# AINx4.net
KiCad netlist of a schematic drawn in EAGLE
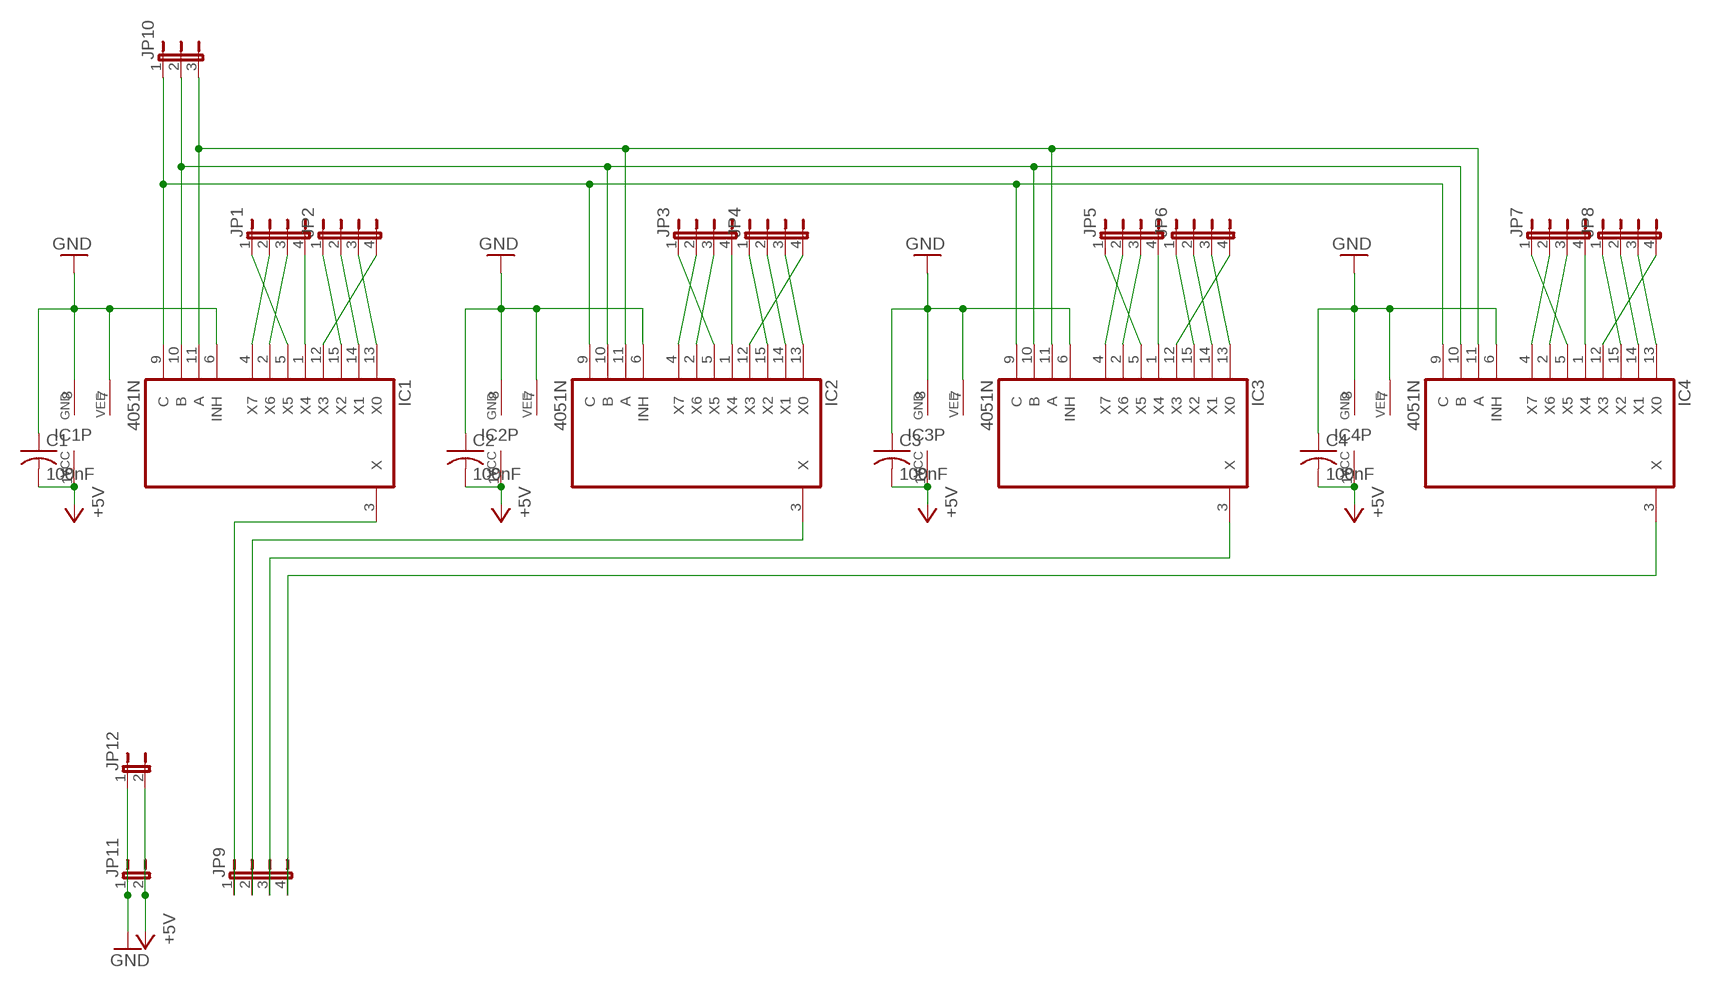
[diagram p0: schematic, sheet 1]

(export (version "E")
  (design (tool "Eeschema 10.0.6"))
  (components
    (comp (ref "C1")
      (value "100nF")
      (footprint "eagle-import:C025-025X050")
      (libsource (lib "eagle-import") (part "C-US025-025X050"))
    )
    (comp (ref "C2")
      (value "100nF")
      (footprint "eagle-import:C025-025X050")
      (libsource (lib "eagle-import") (part "C-US025-025X050"))
    )
    (comp (ref "C3")
      (value "100nF")
      (footprint "eagle-import:C025-025X050")
      (libsource (lib "eagle-import") (part "C-US025-025X050"))
    )
    (comp (ref "C4")
      (value "100nF")
      (footprint "eagle-import:C025-025X050")
      (libsource (lib "eagle-import") (part "C-US025-025X050"))
    )
    (comp (ref "IC1")
      (value "4051N")
      (footprint "eagle-import:DIL16")
      (libsource (lib "eagle-import") (part "4051N"))
    )
    (comp (ref "IC2")
      (value "4051N")
      (footprint "eagle-import:DIL16")
      (libsource (lib "eagle-import") (part "4051N"))
    )
    (comp (ref "IC3")
      (value "4051N")
      (footprint "eagle-import:DIL16")
      (libsource (lib "eagle-import") (part "4051N"))
    )
    (comp (ref "IC4")
      (value "4051N")
      (footprint "eagle-import:DIL16")
      (libsource (lib "eagle-import") (part "4051N"))
    )
    (comp (ref "JP1")
      (value "JP4E")
      (footprint "eagle-import:JP4")
      (libsource (lib "eagle-import") (part "JP4E"))
    )
    (comp (ref "JP2")
      (value "JP4E")
      (footprint "eagle-import:JP4")
      (libsource (lib "eagle-import") (part "JP4E"))
    )
    (comp (ref "JP3")
      (value "JP4E")
      (footprint "eagle-import:JP4")
      (libsource (lib "eagle-import") (part "JP4E"))
    )
    (comp (ref "JP4")
      (value "JP4E")
      (footprint "eagle-import:JP4")
      (libsource (lib "eagle-import") (part "JP4E"))
    )
    (comp (ref "JP5")
      (value "JP4E")
      (footprint "eagle-import:JP4")
      (libsource (lib "eagle-import") (part "JP4E"))
    )
    (comp (ref "JP6")
      (value "JP4E")
      (footprint "eagle-import:JP4")
      (libsource (lib "eagle-import") (part "JP4E"))
    )
    (comp (ref "JP7")
      (value "JP4E")
      (footprint "eagle-import:JP4")
      (libsource (lib "eagle-import") (part "JP4E"))
    )
    (comp (ref "JP8")
      (value "JP4E")
      (footprint "eagle-import:JP4")
      (libsource (lib "eagle-import") (part "JP4E"))
    )
    (comp (ref "JP9")
      (value "JP4E")
      (footprint "eagle-import:JP4")
      (libsource (lib "eagle-import") (part "JP4E"))
    )
    (comp (ref "JP10")
      (value "JP2E")
      (footprint "eagle-import:JP2")
      (libsource (lib "eagle-import") (part "JP2E"))
    )
    (comp (ref "JP11")
      (value "JP1E")
      (footprint "eagle-import:JP1")
      (libsource (lib "eagle-import") (part "JP1E"))
    )
    (comp (ref "JP12")
      (value "JP1E")
      (footprint "eagle-import:JP1")
      (libsource (lib "eagle-import") (part "JP1E"))
    )
  )
  (nets
    (net (code "1") (name "+5V") (class "Default")
      (node (ref "C1") (pin "2") (pinfunction "2_2") (pintype "passive"))
      (node (ref "C2") (pin "2") (pinfunction "2_2") (pintype "passive"))
      (node (ref "C3") (pin "2") (pinfunction "2_2") (pintype "passive"))
      (node (ref "C4") (pin "2") (pinfunction "2_2") (pintype "passive"))
      (node (ref "IC1") (pin "16") (pinfunction "VCC_16") (pintype "power_in"))
      (node (ref "IC2") (pin "16") (pinfunction "VCC_16") (pintype "power_in"))
      (node (ref "IC3") (pin "16") (pinfunction "VCC_16") (pintype "power_in"))
      (node (ref "IC4") (pin "16") (pinfunction "VCC_16") (pintype "power_in"))
      (node (ref "JP11") (pin "2") (pinfunction "2_2") (pintype "passive"))
      (node (ref "JP12") (pin "2") (pinfunction "2_2") (pintype "passive"))
    )
    (net (code "2") (name "GND") (class "Default")
      (node (ref "C1") (pin "1") (pinfunction "1_1") (pintype "passive"))
      (node (ref "C2") (pin "1") (pinfunction "1_1") (pintype "passive"))
      (node (ref "C3") (pin "1") (pinfunction "1_1") (pintype "passive"))
      (node (ref "C4") (pin "1") (pinfunction "1_1") (pintype "passive"))
      (node (ref "IC1") (pin "6") (pinfunction "INH_6") (pintype "input"))
      (node (ref "IC1") (pin "7") (pinfunction "VEE_7") (pintype "power_in"))
      (node (ref "IC1") (pin "8") (pinfunction "GND_8") (pintype "power_in"))
      (node (ref "IC2") (pin "6") (pinfunction "INH_6") (pintype "input"))
      (node (ref "IC2") (pin "7") (pinfunction "VEE_7") (pintype "power_in"))
      (node (ref "IC2") (pin "8") (pinfunction "GND_8") (pintype "power_in"))
      (node (ref "IC3") (pin "6") (pinfunction "INH_6") (pintype "input"))
      (node (ref "IC3") (pin "7") (pinfunction "VEE_7") (pintype "power_in"))
      (node (ref "IC3") (pin "8") (pinfunction "GND_8") (pintype "power_in"))
      (node (ref "IC4") (pin "6") (pinfunction "INH_6") (pintype "input"))
      (node (ref "IC4") (pin "7") (pinfunction "VEE_7") (pintype "power_in"))
      (node (ref "IC4") (pin "8") (pinfunction "GND_8") (pintype "power_in"))
      (node (ref "JP11") (pin "1") (pinfunction "1_1") (pintype "passive"))
      (node (ref "JP12") (pin "1") (pinfunction "1_1") (pintype "passive"))
    )
    (net (code "3") (name "Net-(IC1A-A)") (class "Default")
      (node (ref "IC1") (pin "11") (pinfunction "A_11") (pintype "input"))
      (node (ref "IC2") (pin "11") (pinfunction "A_11") (pintype "input"))
      (node (ref "IC3") (pin "11") (pinfunction "A_11") (pintype "input"))
      (node (ref "IC4") (pin "11") (pinfunction "A_11") (pintype "input"))
      (node (ref "JP10") (pin "3") (pinfunction "3_3") (pintype "passive"))
    )
    (net (code "4") (name "Net-(IC1A-B)") (class "Default")
      (node (ref "IC1") (pin "10") (pinfunction "B_10") (pintype "input"))
      (node (ref "IC2") (pin "10") (pinfunction "B_10") (pintype "input"))
      (node (ref "IC3") (pin "10") (pinfunction "B_10") (pintype "input"))
      (node (ref "IC4") (pin "10") (pinfunction "B_10") (pintype "input"))
      (node (ref "JP10") (pin "2") (pinfunction "2_2") (pintype "passive"))
    )
    (net (code "5") (name "Net-(IC1A-C)") (class "Default")
      (node (ref "IC1") (pin "9") (pinfunction "C_9") (pintype "input"))
      (node (ref "IC2") (pin "9") (pinfunction "C_9") (pintype "input"))
      (node (ref "IC3") (pin "9") (pinfunction "C_9") (pintype "input"))
      (node (ref "IC4") (pin "9") (pinfunction "C_9") (pintype "input"))
      (node (ref "JP10") (pin "1") (pinfunction "1_1") (pintype "passive"))
    )
    (net (code "6") (name "Net-(IC1A-X)") (class "Default")
      (node (ref "IC1") (pin "3") (pinfunction "X_3") (pintype "bidirectional"))
      (node (ref "JP9") (pin "1") (pinfunction "1_1") (pintype "passive"))
    )
    (net (code "7") (name "Net-(IC1A-X0)") (class "Default")
      (node (ref "IC1") (pin "13") (pinfunction "X0_13") (pintype "bidirectional"))
      (node (ref "JP2") (pin "3") (pinfunction "3_3") (pintype "passive"))
    )
    (net (code "8") (name "Net-(IC1A-X1)") (class "Default")
      (node (ref "IC1") (pin "14") (pinfunction "X1_14") (pintype "bidirectional"))
      (node (ref "JP2") (pin "2") (pinfunction "2_2") (pintype "passive"))
    )
    (net (code "9") (name "Net-(IC1A-X2)") (class "Default")
      (node (ref "IC1") (pin "15") (pinfunction "X2_15") (pintype "bidirectional"))
      (node (ref "JP2") (pin "1") (pinfunction "1_1") (pintype "passive"))
    )
    (net (code "10") (name "Net-(IC1A-X3)") (class "Default")
      (node (ref "IC1") (pin "12") (pinfunction "X3_12") (pintype "bidirectional"))
      (node (ref "JP2") (pin "4") (pinfunction "4_4") (pintype "passive"))
    )
    (net (code "11") (name "Net-(IC1A-X4)") (class "Default")
      (node (ref "IC1") (pin "1") (pinfunction "X4_1") (pintype "bidirectional"))
      (node (ref "JP1") (pin "4") (pinfunction "4_4") (pintype "passive"))
    )
    (net (code "12") (name "Net-(IC1A-X5)") (class "Default")
      (node (ref "IC1") (pin "5") (pinfunction "X5_5") (pintype "bidirectional"))
      (node (ref "JP1") (pin "1") (pinfunction "1_1") (pintype "passive"))
    )
    (net (code "13") (name "Net-(IC1A-X6)") (class "Default")
      (node (ref "IC1") (pin "2") (pinfunction "X6_2") (pintype "bidirectional"))
      (node (ref "JP1") (pin "3") (pinfunction "3_3") (pintype "passive"))
    )
    (net (code "14") (name "Net-(IC1A-X7)") (class "Default")
      (node (ref "IC1") (pin "4") (pinfunction "X7_4") (pintype "bidirectional"))
      (node (ref "JP1") (pin "2") (pinfunction "2_2") (pintype "passive"))
    )
    (net (code "15") (name "Net-(IC2A-X)") (class "Default")
      (node (ref "IC2") (pin "3") (pinfunction "X_3") (pintype "bidirectional"))
      (node (ref "JP9") (pin "2") (pinfunction "2_2") (pintype "passive"))
    )
    (net (code "16") (name "Net-(IC2A-X0)") (class "Default")
      (node (ref "IC2") (pin "13") (pinfunction "X0_13") (pintype "bidirectional"))
      (node (ref "JP4") (pin "3") (pinfunction "3_3") (pintype "passive"))
    )
    (net (code "17") (name "Net-(IC2A-X1)") (class "Default")
      (node (ref "IC2") (pin "14") (pinfunction "X1_14") (pintype "bidirectional"))
      (node (ref "JP4") (pin "2") (pinfunction "2_2") (pintype "passive"))
    )
    (net (code "18") (name "Net-(IC2A-X2)") (class "Default")
      (node (ref "IC2") (pin "15") (pinfunction "X2_15") (pintype "bidirectional"))
      (node (ref "JP4") (pin "1") (pinfunction "1_1") (pintype "passive"))
    )
    (net (code "19") (name "Net-(IC2A-X3)") (class "Default")
      (node (ref "IC2") (pin "12") (pinfunction "X3_12") (pintype "bidirectional"))
      (node (ref "JP4") (pin "4") (pinfunction "4_4") (pintype "passive"))
    )
    (net (code "20") (name "Net-(IC2A-X4)") (class "Default")
      (node (ref "IC2") (pin "1") (pinfunction "X4_1") (pintype "bidirectional"))
      (node (ref "JP3") (pin "4") (pinfunction "4_4") (pintype "passive"))
    )
    (net (code "21") (name "Net-(IC2A-X5)") (class "Default")
      (node (ref "IC2") (pin "5") (pinfunction "X5_5") (pintype "bidirectional"))
      (node (ref "JP3") (pin "1") (pinfunction "1_1") (pintype "passive"))
    )
    (net (code "22") (name "Net-(IC2A-X6)") (class "Default")
      (node (ref "IC2") (pin "2") (pinfunction "X6_2") (pintype "bidirectional"))
      (node (ref "JP3") (pin "3") (pinfunction "3_3") (pintype "passive"))
    )
    (net (code "23") (name "Net-(IC2A-X7)") (class "Default")
      (node (ref "IC2") (pin "4") (pinfunction "X7_4") (pintype "bidirectional"))
      (node (ref "JP3") (pin "2") (pinfunction "2_2") (pintype "passive"))
    )
    (net (code "24") (name "Net-(IC3A-X)") (class "Default")
      (node (ref "IC3") (pin "3") (pinfunction "X_3") (pintype "bidirectional"))
      (node (ref "JP9") (pin "3") (pinfunction "3_3") (pintype "passive"))
    )
    (net (code "25") (name "Net-(IC3A-X0)") (class "Default")
      (node (ref "IC3") (pin "13") (pinfunction "X0_13") (pintype "bidirectional"))
      (node (ref "JP6") (pin "3") (pinfunction "3_3") (pintype "passive"))
    )
    (net (code "26") (name "Net-(IC3A-X1)") (class "Default")
      (node (ref "IC3") (pin "14") (pinfunction "X1_14") (pintype "bidirectional"))
      (node (ref "JP6") (pin "2") (pinfunction "2_2") (pintype "passive"))
    )
    (net (code "27") (name "Net-(IC3A-X2)") (class "Default")
      (node (ref "IC3") (pin "15") (pinfunction "X2_15") (pintype "bidirectional"))
      (node (ref "JP6") (pin "1") (pinfunction "1_1") (pintype "passive"))
    )
    (net (code "28") (name "Net-(IC3A-X3)") (class "Default")
      (node (ref "IC3") (pin "12") (pinfunction "X3_12") (pintype "bidirectional"))
      (node (ref "JP6") (pin "4") (pinfunction "4_4") (pintype "passive"))
    )
    (net (code "29") (name "Net-(IC3A-X4)") (class "Default")
      (node (ref "IC3") (pin "1") (pinfunction "X4_1") (pintype "bidirectional"))
      (node (ref "JP5") (pin "4") (pinfunction "4_4") (pintype "passive"))
    )
    (net (code "30") (name "Net-(IC3A-X5)") (class "Default")
      (node (ref "IC3") (pin "5") (pinfunction "X5_5") (pintype "bidirectional"))
      (node (ref "JP5") (pin "1") (pinfunction "1_1") (pintype "passive"))
    )
    (net (code "31") (name "Net-(IC3A-X6)") (class "Default")
      (node (ref "IC3") (pin "2") (pinfunction "X6_2") (pintype "bidirectional"))
      (node (ref "JP5") (pin "3") (pinfunction "3_3") (pintype "passive"))
    )
    (net (code "32") (name "Net-(IC3A-X7)") (class "Default")
      (node (ref "IC3") (pin "4") (pinfunction "X7_4") (pintype "bidirectional"))
      (node (ref "JP5") (pin "2") (pinfunction "2_2") (pintype "passive"))
    )
    (net (code "33") (name "Net-(IC4A-X)") (class "Default")
      (node (ref "IC4") (pin "3") (pinfunction "X_3") (pintype "bidirectional"))
      (node (ref "JP9") (pin "4") (pinfunction "4_4") (pintype "passive"))
    )
    (net (code "34") (name "Net-(IC4A-X0)") (class "Default")
      (node (ref "IC4") (pin "13") (pinfunction "X0_13") (pintype "bidirectional"))
      (node (ref "JP8") (pin "3") (pinfunction "3_3") (pintype "passive"))
    )
    (net (code "35") (name "Net-(IC4A-X1)") (class "Default")
      (node (ref "IC4") (pin "14") (pinfunction "X1_14") (pintype "bidirectional"))
      (node (ref "JP8") (pin "2") (pinfunction "2_2") (pintype "passive"))
    )
    (net (code "36") (name "Net-(IC4A-X2)") (class "Default")
      (node (ref "IC4") (pin "15") (pinfunction "X2_15") (pintype "bidirectional"))
      (node (ref "JP8") (pin "1") (pinfunction "1_1") (pintype "passive"))
    )
    (net (code "37") (name "Net-(IC4A-X3)") (class "Default")
      (node (ref "IC4") (pin "12") (pinfunction "X3_12") (pintype "bidirectional"))
      (node (ref "JP8") (pin "4") (pinfunction "4_4") (pintype "passive"))
    )
    (net (code "38") (name "Net-(IC4A-X4)") (class "Default")
      (node (ref "IC4") (pin "1") (pinfunction "X4_1") (pintype "bidirectional"))
      (node (ref "JP7") (pin "4") (pinfunction "4_4") (pintype "passive"))
    )
    (net (code "39") (name "Net-(IC4A-X5)") (class "Default")
      (node (ref "IC4") (pin "5") (pinfunction "X5_5") (pintype "bidirectional"))
      (node (ref "JP7") (pin "1") (pinfunction "1_1") (pintype "passive"))
    )
    (net (code "40") (name "Net-(IC4A-X6)") (class "Default")
      (node (ref "IC4") (pin "2") (pinfunction "X6_2") (pintype "bidirectional"))
      (node (ref "JP7") (pin "3") (pinfunction "3_3") (pintype "passive"))
    )
    (net (code "41") (name "Net-(IC4A-X7)") (class "Default")
      (node (ref "IC4") (pin "4") (pinfunction "X7_4") (pintype "bidirectional"))
      (node (ref "JP7") (pin "2") (pinfunction "2_2") (pintype "passive"))
    )
  )
)
